# vl4e3.net
KiCad netlist of a schematic drawn in EAGLE
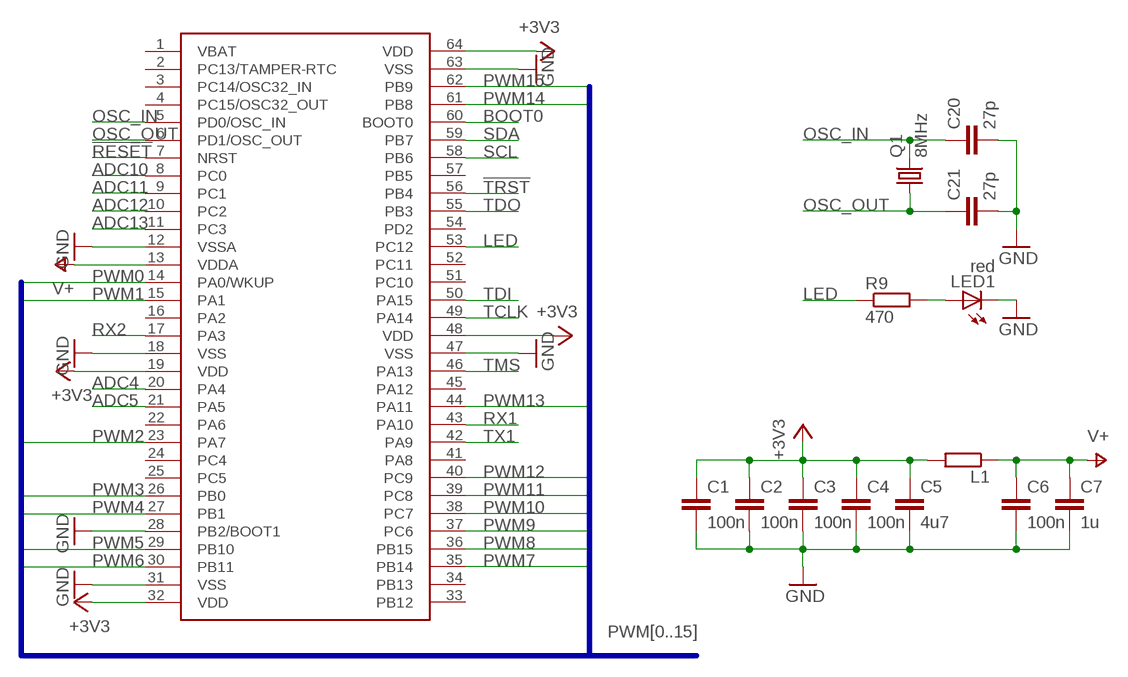
[diagram p0: schematic, sheet 1]
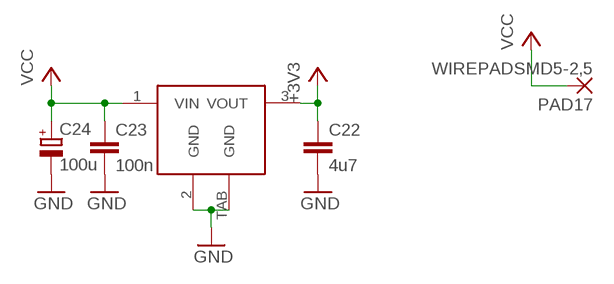
[diagram p1: schematic, sheet 2]
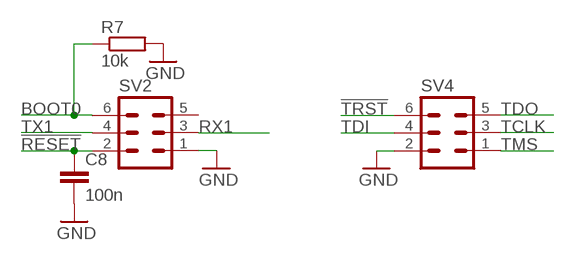
[diagram p2: schematic, sheet 3]
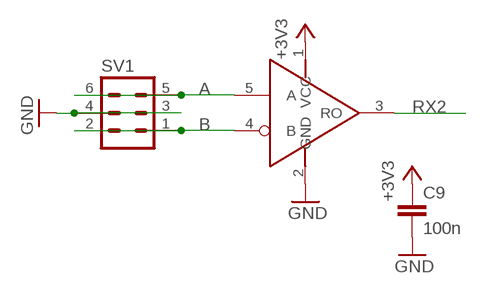
[diagram p3: schematic, sheet 4]
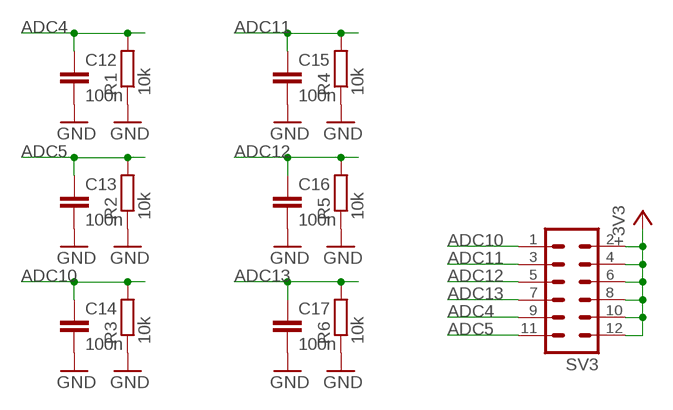
[diagram p4: schematic, sheet 5]
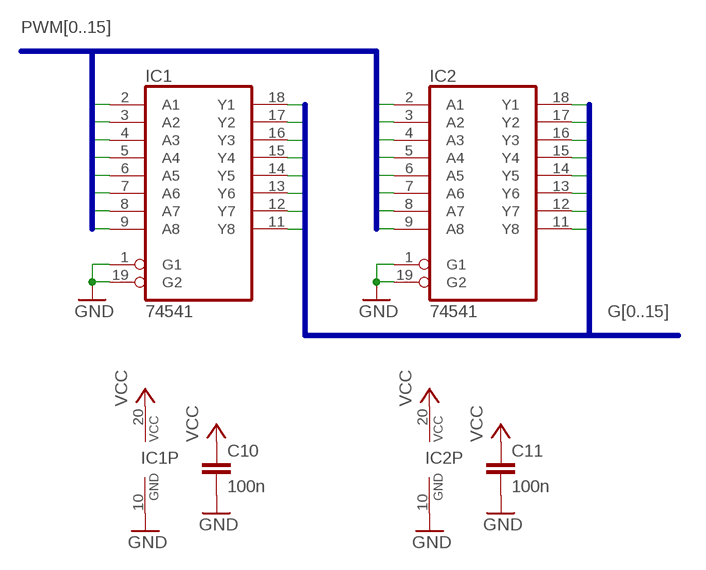
[diagram p5: schematic, sheet 6]
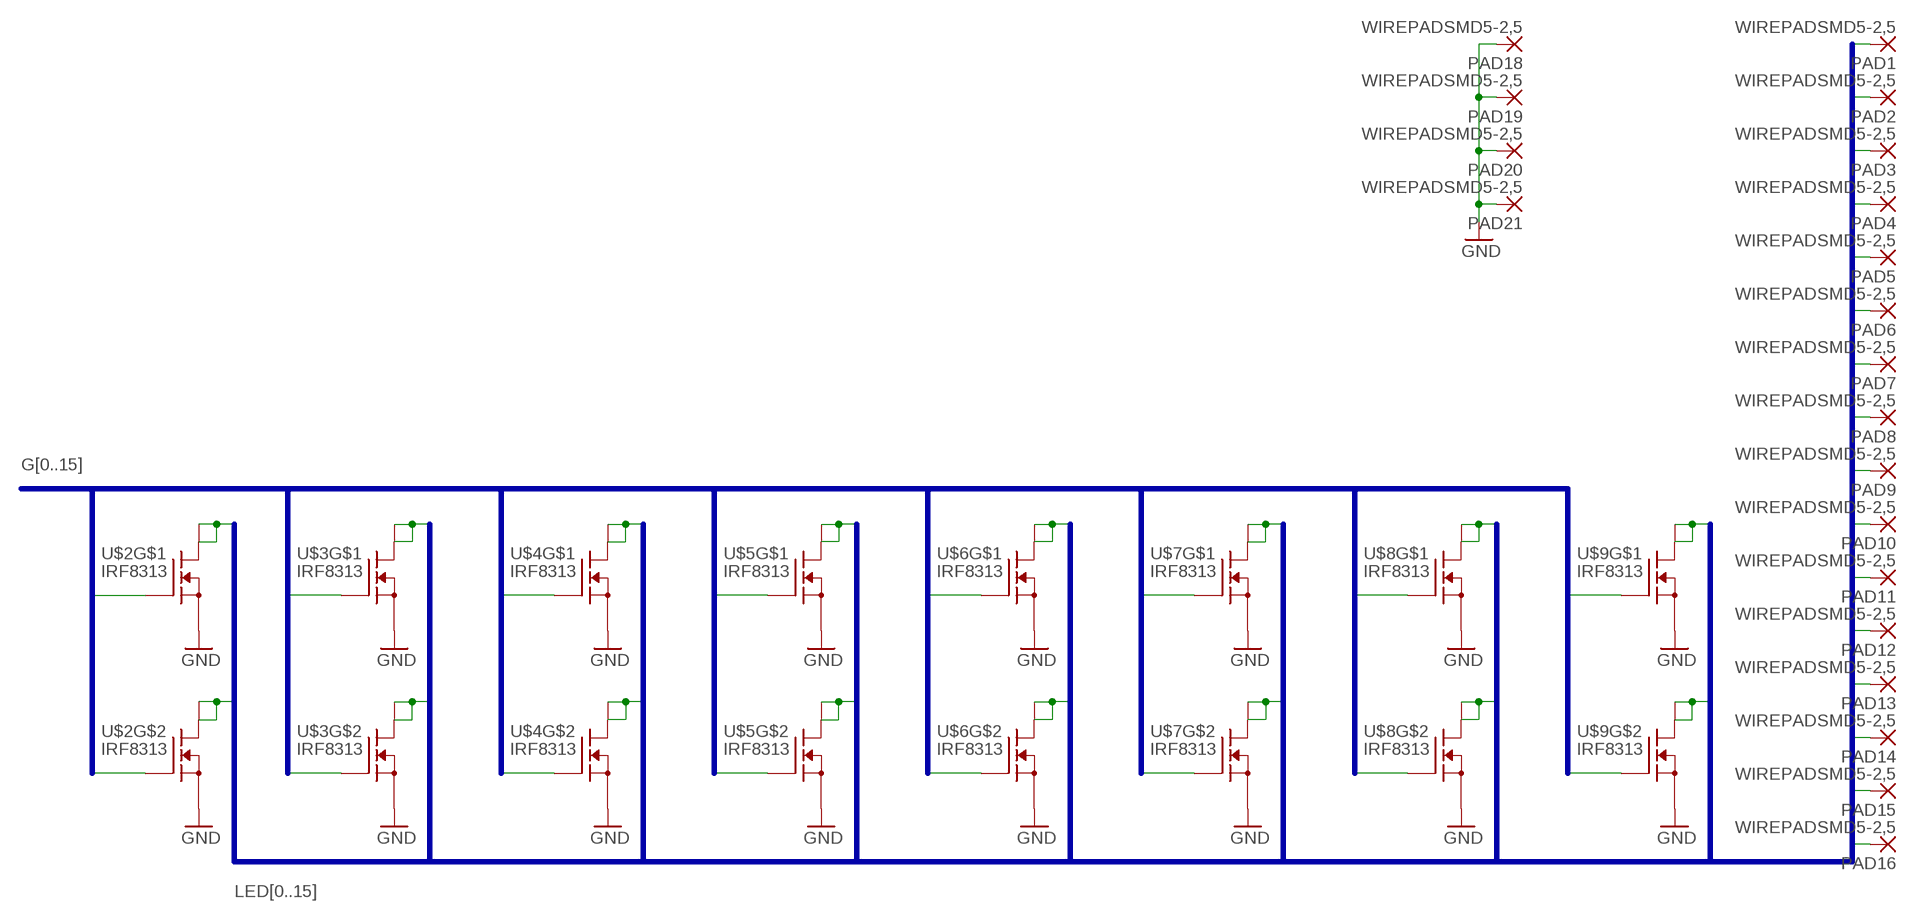
[diagram p6: schematic, sheet 7]

(export (version "E")
  (design (tool "Eeschema 10.0.6"))
  (components
    (comp (ref "C9")
      (value "100n")
      (footprint "eagle-import:C0603")
      (libsource (lib "eagle-import") (part "C-EUC0603"))
    )
    (comp (ref "SV1")
      (value "MA03-2")
      (footprint "eagle-import:MA03-2")
      (libsource (lib "eagle-import") (part "MA03-2"))
    )
    (comp (ref "U$13")
      (value "ISL3280E")
      (footprint "eagle-import:SOT23-5L")
      (libsource (lib "eagle-import") (part "ISL3280E"))
    )
    (comp (ref "C8")
      (value "100n")
      (footprint "eagle-import:C0603")
      (libsource (lib "eagle-import") (part "C-EUC0603"))
    )
    (comp (ref "R7")
      (value "10k")
      (footprint "eagle-import:R0603")
      (libsource (lib "eagle-import") (part "R-EU_R0603"))
    )
    (comp (ref "SV2")
      (value "MA03-2")
      (footprint "eagle-import:MA03-2")
      (libsource (lib "eagle-import") (part "MA03-2"))
    )
    (comp (ref "SV4")
      (value "MA03-2")
      (footprint "eagle-import:MA03-2")
      (libsource (lib "eagle-import") (part "MA03-2"))
    )
    (comp (ref "C10")
      (value "100n")
      (footprint "eagle-import:C0603")
      (libsource (lib "eagle-import") (part "C-EUC0603"))
    )
    (comp (ref "C11")
      (value "100n")
      (footprint "eagle-import:C0603")
      (libsource (lib "eagle-import") (part "C-EUC0603"))
    )
    (comp (ref "IC1")
      (value "74541")
      (footprint "eagle-import:TSSOP20")
      (libsource (lib "eagle-import") (part "74541"))
    )
    (comp (ref "IC2")
      (value "74541")
      (footprint "eagle-import:TSSOP20")
      (libsource (lib "eagle-import") (part "74541"))
    )
    (comp (ref "C1")
      (value "100n")
      (footprint "eagle-import:C0603")
      (libsource (lib "eagle-import") (part "C-EUC0603"))
    )
    (comp (ref "C2")
      (value "100n")
      (footprint "eagle-import:C0603")
      (libsource (lib "eagle-import") (part "C-EUC0603"))
    )
    (comp (ref "C3")
      (value "100n")
      (footprint "eagle-import:C0603")
      (libsource (lib "eagle-import") (part "C-EUC0603"))
    )
    (comp (ref "C4")
      (value "100n")
      (footprint "eagle-import:C0603")
      (libsource (lib "eagle-import") (part "C-EUC0603"))
    )
    (comp (ref "C5")
      (value "4u7")
      (footprint "eagle-import:C0805")
      (libsource (lib "eagle-import") (part "C-EUC0805"))
    )
    (comp (ref "C6")
      (value "100n")
      (footprint "eagle-import:C0603")
      (libsource (lib "eagle-import") (part "C-EUC0603"))
    )
    (comp (ref "C7")
      (value "1u")
      (footprint "eagle-import:C0805")
      (libsource (lib "eagle-import") (part "C-EUC0805"))
    )
    (comp (ref "C20")
      (value "27p")
      (footprint "eagle-import:C0603")
      (libsource (lib "eagle-import") (part "C-EUC0603"))
    )
    (comp (ref "C21")
      (value "27p")
      (footprint "eagle-import:C0603")
      (libsource (lib "eagle-import") (part "C-EUC0603"))
    )
    (comp (ref "L1")
      (value "R-EU_R0805")
      (footprint "eagle-import:R0805")
      (libsource (lib "eagle-import") (part "R-EU_R0805"))
    )
    (comp (ref "LED1")
      (value "red")
      (footprint "eagle-import:CHIPLED_0805")
      (libsource (lib "eagle-import") (part "LEDCHIPLED_0805"))
    )
    (comp (ref "Q1")
      (value "8MHz")
      (footprint "eagle-import:HC49_S")
      (libsource (lib "eagle-import") (part "CRYSTALHC49S"))
    )
    (comp (ref "R9")
      (value "470")
      (footprint "eagle-import:R0805")
      (libsource (lib "eagle-import") (part "R-EU_R0805"))
    )
    (comp (ref "U$1")
      (value "STM32F100R")
      (footprint "eagle-import:TQFP64-10X10")
      (libsource (lib "eagle-import") (part "STM32F100R"))
    )
    (comp (ref "PAD1")
      (value "WIREPADSMD5-2,5")
      (footprint "eagle-import:5-2,5")
      (libsource (lib "eagle-import") (part "WIREPADSMD5-2,5"))
    )
    (comp (ref "PAD2")
      (value "WIREPADSMD5-2,5")
      (footprint "eagle-import:5-2,5")
      (libsource (lib "eagle-import") (part "WIREPADSMD5-2,5"))
    )
    (comp (ref "PAD3")
      (value "WIREPADSMD5-2,5")
      (footprint "eagle-import:5-2,5")
      (libsource (lib "eagle-import") (part "WIREPADSMD5-2,5"))
    )
    (comp (ref "PAD4")
      (value "WIREPADSMD5-2,5")
      (footprint "eagle-import:5-2,5")
      (libsource (lib "eagle-import") (part "WIREPADSMD5-2,5"))
    )
    (comp (ref "PAD5")
      (value "WIREPADSMD5-2,5")
      (footprint "eagle-import:5-2,5")
      (libsource (lib "eagle-import") (part "WIREPADSMD5-2,5"))
    )
    (comp (ref "PAD6")
      (value "WIREPADSMD5-2,5")
      (footprint "eagle-import:5-2,5")
      (libsource (lib "eagle-import") (part "WIREPADSMD5-2,5"))
    )
    (comp (ref "PAD7")
      (value "WIREPADSMD5-2,5")
      (footprint "eagle-import:5-2,5")
      (libsource (lib "eagle-import") (part "WIREPADSMD5-2,5"))
    )
    (comp (ref "PAD8")
      (value "WIREPADSMD5-2,5")
      (footprint "eagle-import:5-2,5")
      (libsource (lib "eagle-import") (part "WIREPADSMD5-2,5"))
    )
    (comp (ref "PAD9")
      (value "WIREPADSMD5-2,5")
      (footprint "eagle-import:5-2,5")
      (libsource (lib "eagle-import") (part "WIREPADSMD5-2,5"))
    )
    (comp (ref "PAD10")
      (value "WIREPADSMD5-2,5")
      (footprint "eagle-import:5-2,5")
      (libsource (lib "eagle-import") (part "WIREPADSMD5-2,5"))
    )
    (comp (ref "PAD11")
      (value "WIREPADSMD5-2,5")
      (footprint "eagle-import:5-2,5")
      (libsource (lib "eagle-import") (part "WIREPADSMD5-2,5"))
    )
    (comp (ref "PAD12")
      (value "WIREPADSMD5-2,5")
      (footprint "eagle-import:5-2,5")
      (libsource (lib "eagle-import") (part "WIREPADSMD5-2,5"))
    )
    (comp (ref "PAD13")
      (value "WIREPADSMD5-2,5")
      (footprint "eagle-import:5-2,5")
      (libsource (lib "eagle-import") (part "WIREPADSMD5-2,5"))
    )
    (comp (ref "PAD14")
      (value "WIREPADSMD5-2,5")
      (footprint "eagle-import:5-2,5")
      (libsource (lib "eagle-import") (part "WIREPADSMD5-2,5"))
    )
    (comp (ref "PAD15")
      (value "WIREPADSMD5-2,5")
      (footprint "eagle-import:5-2,5")
      (libsource (lib "eagle-import") (part "WIREPADSMD5-2,5"))
    )
    (comp (ref "PAD16")
      (value "WIREPADSMD5-2,5")
      (footprint "eagle-import:5-2,5")
      (libsource (lib "eagle-import") (part "WIREPADSMD5-2,5"))
    )
    (comp (ref "PAD18")
      (value "WIREPADSMD5-2,5")
      (footprint "eagle-import:5-2,5")
      (libsource (lib "eagle-import") (part "WIREPADSMD5-2,5"))
    )
    (comp (ref "PAD19")
      (value "WIREPADSMD5-2,5")
      (footprint "eagle-import:5-2,5")
      (libsource (lib "eagle-import") (part "WIREPADSMD5-2,5"))
    )
    (comp (ref "PAD20")
      (value "WIREPADSMD5-2,5")
      (footprint "eagle-import:5-2,5")
      (libsource (lib "eagle-import") (part "WIREPADSMD5-2,5"))
    )
    (comp (ref "PAD21")
      (value "WIREPADSMD5-2,5")
      (footprint "eagle-import:5-2,5")
      (libsource (lib "eagle-import") (part "WIREPADSMD5-2,5"))
    )
    (comp (ref "U$2")
      (value "IRF8313")
      (footprint "eagle-import:SO-08")
      (libsource (lib "eagle-import") (part "IRF8313"))
    )
    (comp (ref "U$3")
      (value "IRF8313")
      (footprint "eagle-import:SO-08")
      (libsource (lib "eagle-import") (part "IRF8313"))
    )
    (comp (ref "U$4")
      (value "IRF8313")
      (footprint "eagle-import:SO-08")
      (libsource (lib "eagle-import") (part "IRF8313"))
    )
    (comp (ref "U$5")
      (value "IRF8313")
      (footprint "eagle-import:SO-08")
      (libsource (lib "eagle-import") (part "IRF8313"))
    )
    (comp (ref "U$6")
      (value "IRF8313")
      (footprint "eagle-import:SO-08")
      (libsource (lib "eagle-import") (part "IRF8313"))
    )
    (comp (ref "U$7")
      (value "IRF8313")
      (footprint "eagle-import:SO-08")
      (libsource (lib "eagle-import") (part "IRF8313"))
    )
    (comp (ref "U$8")
      (value "IRF8313")
      (footprint "eagle-import:SO-08")
      (libsource (lib "eagle-import") (part "IRF8313"))
    )
    (comp (ref "U$9")
      (value "IRF8313")
      (footprint "eagle-import:SO-08")
      (libsource (lib "eagle-import") (part "IRF8313"))
    )
    (comp (ref "C22")
      (value "4u7")
      (footprint "eagle-import:C0805")
      (libsource (lib "eagle-import") (part "C-EUC0805"))
    )
    (comp (ref "C23")
      (value "100n")
      (footprint "eagle-import:C0603")
      (libsource (lib "eagle-import") (part "C-EUC0603"))
    )
    (comp (ref "C24")
      (value "100u")
      (footprint "eagle-import:E2,5-6")
      (libsource (lib "eagle-import") (part "CPOL-EUE2.5-6"))
    )
    (comp (ref "PAD17")
      (value "WIREPADSMD5-2,5")
      (footprint "eagle-import:5-2,5")
      (libsource (lib "eagle-import") (part "WIREPADSMD5-2,5"))
    )
    (comp (ref "U$10")
      (value "MIC5209")
      (footprint "eagle-import:SOT223")
      (libsource (lib "eagle-import") (part "MIC5209"))
    )
    (comp (ref "C12")
      (value "100n")
      (footprint "eagle-import:C0603")
      (libsource (lib "eagle-import") (part "C-EUC0603"))
    )
    (comp (ref "C13")
      (value "100n")
      (footprint "eagle-import:C0603")
      (libsource (lib "eagle-import") (part "C-EUC0603"))
    )
    (comp (ref "C14")
      (value "100n")
      (footprint "eagle-import:C0603")
      (libsource (lib "eagle-import") (part "C-EUC0603"))
    )
    (comp (ref "C15")
      (value "100n")
      (footprint "eagle-import:C0603")
      (libsource (lib "eagle-import") (part "C-EUC0603"))
    )
    (comp (ref "C16")
      (value "100n")
      (footprint "eagle-import:C0603")
      (libsource (lib "eagle-import") (part "C-EUC0603"))
    )
    (comp (ref "C17")
      (value "100n")
      (footprint "eagle-import:C0603")
      (libsource (lib "eagle-import") (part "C-EUC0603"))
    )
    (comp (ref "R1")
      (value "10k")
      (footprint "eagle-import:R0603")
      (libsource (lib "eagle-import") (part "R-EU_R0603"))
    )
    (comp (ref "R2")
      (value "10k")
      (footprint "eagle-import:R0603")
      (libsource (lib "eagle-import") (part "R-EU_R0603"))
    )
    (comp (ref "R3")
      (value "10k")
      (footprint "eagle-import:R0603")
      (libsource (lib "eagle-import") (part "R-EU_R0603"))
    )
    (comp (ref "R4")
      (value "10k")
      (footprint "eagle-import:R0603")
      (libsource (lib "eagle-import") (part "R-EU_R0603"))
    )
    (comp (ref "R5")
      (value "10k")
      (footprint "eagle-import:R0603")
      (libsource (lib "eagle-import") (part "R-EU_R0603"))
    )
    (comp (ref "R6")
      (value "10k")
      (footprint "eagle-import:R0603")
      (libsource (lib "eagle-import") (part "R-EU_R0603"))
    )
    (comp (ref "SV3")
      (value "MA06-2")
      (footprint "eagle-import:MA06-2")
      (libsource (lib "eagle-import") (part "MA06-2"))
    )
  )
  (nets
    (net (code "1") (name "+3V3") (class "Default")
      (node (ref "C1") (pin "1") (pinfunction "1_1") (pintype "passive"))
      (node (ref "C2") (pin "1") (pinfunction "1_1") (pintype "passive"))
      (node (ref "C22") (pin "1") (pinfunction "1_1") (pintype "passive"))
      (node (ref "C3") (pin "1") (pinfunction "1_1") (pintype "passive"))
      (node (ref "C4") (pin "1") (pinfunction "1_1") (pintype "passive"))
      (node (ref "C5") (pin "1") (pinfunction "1_1") (pintype "passive"))
      (node (ref "C9") (pin "1") (pinfunction "1_1") (pintype "passive"))
      (node (ref "L1") (pin "2") (pinfunction "2_2") (pintype "passive"))
      (node (ref "SV3") (pin "10") (pinfunction "10_10") (pintype "passive"))
      (node (ref "SV3") (pin "12") (pinfunction "12_12") (pintype "passive"))
      (node (ref "SV3") (pin "2") (pinfunction "2_2") (pintype "passive"))
      (node (ref "SV3") (pin "4") (pinfunction "4_4") (pintype "passive"))
      (node (ref "SV3") (pin "6") (pinfunction "6_6") (pintype "passive"))
      (node (ref "SV3") (pin "8") (pinfunction "8_8") (pintype "passive"))
      (node (ref "U$1") (pin "19") (pinfunction "VDD_19") (pintype "bidirectional"))
      (node (ref "U$1") (pin "32") (pinfunction "VDD_32") (pintype "bidirectional"))
      (node (ref "U$1") (pin "48") (pinfunction "VDD_48") (pintype "bidirectional"))
      (node (ref "U$1") (pin "64") (pinfunction "VDD_64") (pintype "bidirectional"))
      (node (ref "U$10") (pin "3") (pinfunction "VOUT_3") (pintype "bidirectional"))
      (node (ref "U$13") (pin "1") (pinfunction "VCC_1") (pintype "power_in"))
    )
    (net (code "7") (name "A") (class "Default")
      (node (ref "SV1") (pin "5") (pinfunction "5_5") (pintype "passive"))
      (node (ref "SV1") (pin "6") (pinfunction "6_6") (pintype "passive"))
      (node (ref "U$13") (pin "5") (pinfunction "A_5") (pintype "bidirectional"))
    )
    (net (code "8") (name "ADC4") (class "Default")
      (node (ref "C12") (pin "1") (pinfunction "1_1") (pintype "passive"))
      (node (ref "R1") (pin "2") (pinfunction "2_2") (pintype "passive"))
      (node (ref "SV3") (pin "9") (pinfunction "9_9") (pintype "passive"))
      (node (ref "U$1") (pin "20") (pinfunction "PA4_20") (pintype "bidirectional"))
    )
    (net (code "9") (name "ADC5") (class "Default")
      (node (ref "C13") (pin "1") (pinfunction "1_1") (pintype "passive"))
      (node (ref "R2") (pin "2") (pinfunction "2_2") (pintype "passive"))
      (node (ref "SV3") (pin "11") (pinfunction "11_11") (pintype "passive"))
      (node (ref "U$1") (pin "21") (pinfunction "PA5_21") (pintype "bidirectional"))
    )
    (net (code "10") (name "ADC10") (class "Default")
      (node (ref "C14") (pin "1") (pinfunction "1_1") (pintype "passive"))
      (node (ref "R3") (pin "2") (pinfunction "2_2") (pintype "passive"))
      (node (ref "SV3") (pin "1") (pinfunction "1_1") (pintype "passive"))
      (node (ref "U$1") (pin "8") (pinfunction "PC0_8") (pintype "bidirectional"))
    )
    (net (code "11") (name "ADC11") (class "Default")
      (node (ref "C15") (pin "1") (pinfunction "1_1") (pintype "passive"))
      (node (ref "R4") (pin "2") (pinfunction "2_2") (pintype "passive"))
      (node (ref "SV3") (pin "3") (pinfunction "3_3") (pintype "passive"))
      (node (ref "U$1") (pin "9") (pinfunction "PC1_9") (pintype "bidirectional"))
    )
    (net (code "12") (name "ADC12") (class "Default")
      (node (ref "C16") (pin "1") (pinfunction "1_1") (pintype "passive"))
      (node (ref "R5") (pin "2") (pinfunction "2_2") (pintype "passive"))
      (node (ref "SV3") (pin "5") (pinfunction "5_5") (pintype "passive"))
      (node (ref "U$1") (pin "10") (pinfunction "PC2_10") (pintype "bidirectional"))
    )
    (net (code "13") (name "ADC13") (class "Default")
      (node (ref "C17") (pin "1") (pinfunction "1_1") (pintype "passive"))
      (node (ref "R6") (pin "2") (pinfunction "2_2") (pintype "passive"))
      (node (ref "SV3") (pin "7") (pinfunction "7_7") (pintype "passive"))
      (node (ref "U$1") (pin "11") (pinfunction "PC3_11") (pintype "bidirectional"))
    )
    (net (code "14") (name "B") (class "Default")
      (node (ref "SV1") (pin "1") (pinfunction "1_1") (pintype "passive"))
      (node (ref "SV1") (pin "2") (pinfunction "2_2") (pintype "passive"))
      (node (ref "U$13") (pin "4") (pinfunction "B_4") (pintype "bidirectional"))
    )
    (net (code "15") (name "BOOT0") (class "Default")
      (node (ref "R7") (pin "1") (pinfunction "1_1") (pintype "passive"))
      (node (ref "SV2") (pin "6") (pinfunction "6_6") (pintype "passive"))
      (node (ref "U$1") (pin "60") (pinfunction "BOOT0_60") (pintype "bidirectional"))
    )
    (net (code "16") (name "G0") (class "Default")
      (node (ref "IC1") (pin "18") (pinfunction "Y1_18") (pintype "tri_state"))
      (node (ref "U$2") (pin "2") (pinfunction "G_2") (pintype "passive"))
    )
    (net (code "17") (name "G1") (class "Default")
      (node (ref "IC1") (pin "17") (pinfunction "Y2_17") (pintype "tri_state"))
      (node (ref "U$2") (pin "4") (pinfunction "G_4") (pintype "passive"))
    )
    (net (code "18") (name "G2") (class "Default")
      (node (ref "IC1") (pin "16") (pinfunction "Y3_16") (pintype "tri_state"))
      (node (ref "U$3") (pin "2") (pinfunction "G_2") (pintype "passive"))
    )
    (net (code "19") (name "G3") (class "Default")
      (node (ref "IC1") (pin "15") (pinfunction "Y4_15") (pintype "tri_state"))
      (node (ref "U$3") (pin "4") (pinfunction "G_4") (pintype "passive"))
    )
    (net (code "20") (name "G4") (class "Default")
      (node (ref "IC1") (pin "14") (pinfunction "Y5_14") (pintype "tri_state"))
      (node (ref "U$4") (pin "2") (pinfunction "G_2") (pintype "passive"))
    )
    (net (code "21") (name "G5") (class "Default")
      (node (ref "IC1") (pin "13") (pinfunction "Y6_13") (pintype "tri_state"))
      (node (ref "U$4") (pin "4") (pinfunction "G_4") (pintype "passive"))
    )
    (net (code "22") (name "G6") (class "Default")
      (node (ref "IC1") (pin "12") (pinfunction "Y7_12") (pintype "tri_state"))
      (node (ref "U$5") (pin "2") (pinfunction "G_2") (pintype "passive"))
    )
    (net (code "23") (name "G7") (class "Default")
      (node (ref "IC1") (pin "11") (pinfunction "Y8_11") (pintype "tri_state"))
      (node (ref "U$5") (pin "4") (pinfunction "G_4") (pintype "passive"))
    )
    (net (code "24") (name "G8") (class "Default")
      (node (ref "IC2") (pin "18") (pinfunction "Y1_18") (pintype "tri_state"))
      (node (ref "U$6") (pin "2") (pinfunction "G_2") (pintype "passive"))
    )
    (net (code "25") (name "G9") (class "Default")
      (node (ref "IC2") (pin "17") (pinfunction "Y2_17") (pintype "tri_state"))
      (node (ref "U$6") (pin "4") (pinfunction "G_4") (pintype "passive"))
    )
    (net (code "26") (name "G10") (class "Default")
      (node (ref "IC2") (pin "16") (pinfunction "Y3_16") (pintype "tri_state"))
      (node (ref "U$7") (pin "2") (pinfunction "G_2") (pintype "passive"))
    )
    (net (code "27") (name "G11") (class "Default")
      (node (ref "IC2") (pin "15") (pinfunction "Y4_15") (pintype "tri_state"))
      (node (ref "U$7") (pin "4") (pinfunction "G_4") (pintype "passive"))
    )
    (net (code "28") (name "G12") (class "Default")
      (node (ref "IC2") (pin "14") (pinfunction "Y5_14") (pintype "tri_state"))
      (node (ref "U$8") (pin "2") (pinfunction "G_2") (pintype "passive"))
    )
    (net (code "29") (name "G13") (class "Default")
      (node (ref "IC2") (pin "13") (pinfunction "Y6_13") (pintype "tri_state"))
      (node (ref "U$8") (pin "4") (pinfunction "G_4") (pintype "passive"))
    )
    (net (code "30") (name "G14") (class "Default")
      (node (ref "IC2") (pin "12") (pinfunction "Y7_12") (pintype "tri_state"))
      (node (ref "U$9") (pin "2") (pinfunction "G_2") (pintype "passive"))
    )
    (net (code "31") (name "G15") (class "Default")
      (node (ref "IC2") (pin "11") (pinfunction "Y8_11") (pintype "tri_state"))
      (node (ref "U$9") (pin "4") (pinfunction "G_4") (pintype "passive"))
    )
    (net (code "32") (name "GND") (class "Default")
      (node (ref "C1") (pin "2") (pinfunction "2_2") (pintype "passive"))
      (node (ref "C10") (pin "2") (pinfunction "2_2") (pintype "passive"))
      (node (ref "C11") (pin "2") (pinfunction "2_2") (pintype "passive"))
      (node (ref "C12") (pin "2") (pinfunction "2_2") (pintype "passive"))
      (node (ref "C13") (pin "2") (pinfunction "2_2") (pintype "passive"))
      (node (ref "C14") (pin "2") (pinfunction "2_2") (pintype "passive"))
      (node (ref "C15") (pin "2") (pinfunction "2_2") (pintype "passive"))
      (node (ref "C16") (pin "2") (pinfunction "2_2") (pintype "passive"))
      (node (ref "C17") (pin "2") (pinfunction "2_2") (pintype "passive"))
      (node (ref "C2") (pin "2") (pinfunction "2_2") (pintype "passive"))
      (node (ref "C20") (pin "2") (pinfunction "2_2") (pintype "passive"))
      (node (ref "C21") (pin "2") (pinfunction "2_2") (pintype "passive"))
      (node (ref "C22") (pin "2") (pinfunction "2_2") (pintype "passive"))
      (node (ref "C23") (pin "2") (pinfunction "2_2") (pintype "passive"))
      (node (ref "C24") (pin "-") (pinfunction "-_-") (pintype "passive"))
      (node (ref "C3") (pin "2") (pinfunction "2_2") (pintype "passive"))
      (node (ref "C4") (pin "2") (pinfunction "2_2") (pintype "passive"))
      (node (ref "C5") (pin "2") (pinfunction "2_2") (pintype "passive"))
      (node (ref "C6") (pin "2") (pinfunction "2_2") (pintype "passive"))
      (node (ref "C7") (pin "2") (pinfunction "2_2") (pintype "passive"))
      (node (ref "C8") (pin "2") (pinfunction "2_2") (pintype "passive"))
      (node (ref "C9") (pin "2") (pinfunction "2_2") (pintype "passive"))
      (node (ref "IC1") (pin "1") (pinfunction "G1_1") (pintype "input"))
      (node (ref "IC1") (pin "10") (pinfunction "GND_10") (pintype "power_in"))
      (node (ref "IC1") (pin "19") (pinfunction "G2_19") (pintype "input"))
      (node (ref "IC2") (pin "1") (pinfunction "G1_1") (pintype "input"))
      (node (ref "IC2") (pin "10") (pinfunction "GND_10") (pintype "power_in"))
      (node (ref "IC2") (pin "19") (pinfunction "G2_19") (pintype "input"))
      (node (ref "LED1") (pin "C") (pinfunction "C_C") (pintype "passive"))
      (node (ref "PAD18") (pin "1") (pinfunction "P_1") (pintype "passive"))
      (node (ref "PAD19") (pin "1") (pinfunction "P_1") (pintype "passive"))
      (node (ref "PAD20") (pin "1") (pinfunction "P_1") (pintype "passive"))
      (node (ref "PAD21") (pin "1") (pinfunction "P_1") (pintype "passive"))
      (node (ref "R1") (pin "1") (pinfunction "1_1") (pintype "passive"))
      (node (ref "R2") (pin "1") (pinfunction "1_1") (pintype "passive"))
      (node (ref "R3") (pin "1") (pinfunction "1_1") (pintype "passive"))
      (node (ref "R4") (pin "1") (pinfunction "1_1") (pintype "passive"))
      (node (ref "R5") (pin "1") (pinfunction "1_1") (pintype "passive"))
      (node (ref "R6") (pin "1") (pinfunction "1_1") (pintype "passive"))
      (node (ref "R7") (pin "2") (pinfunction "2_2") (pintype "passive"))
      (node (ref "SV1") (pin "3") (pinfunction "3_3") (pintype "passive"))
      (node (ref "SV1") (pin "4") (pinfunction "4_4") (pintype "passive"))
      (node (ref "SV2") (pin "1") (pinfunction "1_1") (pintype "passive"))
      (node (ref "SV4") (pin "2") (pinfunction "2_2") (pintype "passive"))
      (node (ref "U$1") (pin "12") (pinfunction "VSSA_12") (pintype "bidirectional"))
      (node (ref "U$1") (pin "18") (pinfunction "VSS_18") (pintype "bidirectional"))
      (node (ref "U$1") (pin "28") (pinfunction "PB2/BOOT1_28") (pintype "bidirectional"))
      (node (ref "U$1") (pin "31") (pinfunction "VSS_31") (pintype "bidirectional"))
      (node (ref "U$1") (pin "47") (pinfunction "VSS_47") (pintype "bidirectional"))
      (node (ref "U$1") (pin "63") (pinfunction "VSS_63") (pintype "bidirectional"))
      (node (ref "U$10") (pin "2") (pinfunction "GND_2") (pintype "bidirectional"))
      (node (ref "U$10") (pin "TAB") (pinfunction "GND_TAB") (pintype "bidirectional"))
      (node (ref "U$13") (pin "2") (pinfunction "GND_2") (pintype "power_in"))
      (node (ref "U$2") (pin "1") (pinfunction "S_1") (pintype "passive"))
      (node (ref "U$2") (pin "3") (pinfunction "S_3") (pintype "passive"))
      (node (ref "U$3") (pin "1") (pinfunction "S_1") (pintype "passive"))
      (node (ref "U$3") (pin "3") (pinfunction "S_3") (pintype "passive"))
      (node (ref "U$4") (pin "1") (pinfunction "S_1") (pintype "passive"))
      (node (ref "U$4") (pin "3") (pinfunction "S_3") (pintype "passive"))
      (node (ref "U$5") (pin "1") (pinfunction "S_1") (pintype "passive"))
      (node (ref "U$5") (pin "3") (pinfunction "S_3") (pintype "passive"))
      (node (ref "U$6") (pin "1") (pinfunction "S_1") (pintype "passive"))
      (node (ref "U$6") (pin "3") (pinfunction "S_3") (pintype "passive"))
      (node (ref "U$7") (pin "1") (pinfunction "S_1") (pintype "passive"))
      (node (ref "U$7") (pin "3") (pinfunction "S_3") (pintype "passive"))
      (node (ref "U$8") (pin "1") (pinfunction "S_1") (pintype "passive"))
      (node (ref "U$8") (pin "3") (pinfunction "S_3") (pintype "passive"))
      (node (ref "U$9") (pin "1") (pinfunction "S_1") (pintype "passive"))
      (node (ref "U$9") (pin "3") (pinfunction "S_3") (pintype "passive"))
    )
    (net (code "33") (name "LED") (class "Default")
      (node (ref "R9") (pin "1") (pinfunction "1_1") (pintype "passive"))
      (node (ref "U$1") (pin "53") (pinfunction "PC12_53") (pintype "bidirectional"))
    )
    (net (code "34") (name "LED0") (class "Default")
      (node (ref "PAD1") (pin "1") (pinfunction "P_1") (pintype "passive"))
      (node (ref "U$2") (pin "7") (pinfunction "D_7") (pintype "passive"))
      (node (ref "U$2") (pin "8") (pinfunction "D_8") (pintype "passive"))
    )
    (net (code "35") (name "LED1") (class "Default")
      (node (ref "PAD2") (pin "1") (pinfunction "P_1") (pintype "passive"))
      (node (ref "U$2") (pin "5") (pinfunction "D_5") (pintype "passive"))
      (node (ref "U$2") (pin "6") (pinfunction "D_6") (pintype "passive"))
    )
    (net (code "36") (name "LED2") (class "Default")
      (node (ref "PAD3") (pin "1") (pinfunction "P_1") (pintype "passive"))
      (node (ref "U$3") (pin "7") (pinfunction "D_7") (pintype "passive"))
      (node (ref "U$3") (pin "8") (pinfunction "D_8") (pintype "passive"))
    )
    (net (code "37") (name "LED3") (class "Default")
      (node (ref "PAD4") (pin "1") (pinfunction "P_1") (pintype "passive"))
      (node (ref "U$3") (pin "5") (pinfunction "D_5") (pintype "passive"))
      (node (ref "U$3") (pin "6") (pinfunction "D_6") (pintype "passive"))
    )
    (net (code "38") (name "LED4") (class "Default")
      (node (ref "PAD5") (pin "1") (pinfunction "P_1") (pintype "passive"))
      (node (ref "U$4") (pin "7") (pinfunction "D_7") (pintype "passive"))
      (node (ref "U$4") (pin "8") (pinfunction "D_8") (pintype "passive"))
    )
    (net (code "39") (name "LED5") (class "Default")
      (node (ref "PAD6") (pin "1") (pinfunction "P_1") (pintype "passive"))
      (node (ref "U$4") (pin "5") (pinfunction "D_5") (pintype "passive"))
      (node (ref "U$4") (pin "6") (pinfunction "D_6") (pintype "passive"))
    )
    (net (code "40") (name "LED6") (class "Default")
      (node (ref "PAD7") (pin "1") (pinfunction "P_1") (pintype "passive"))
      (node (ref "U$5") (pin "7") (pinfunction "D_7") (pintype "passive"))
      (node (ref "U$5") (pin "8") (pinfunction "D_8") (pintype "passive"))
    )
    (net (code "41") (name "LED7") (class "Default")
      (node (ref "PAD8") (pin "1") (pinfunction "P_1") (pintype "passive"))
      (node (ref "U$5") (pin "5") (pinfunction "D_5") (pintype "passive"))
      (node (ref "U$5") (pin "6") (pinfunction "D_6") (pintype "passive"))
    )
    (net (code "42") (name "LED8") (class "Default")
      (node (ref "PAD9") (pin "1") (pinfunction "P_1") (pintype "passive"))
      (node (ref "U$6") (pin "7") (pinfunction "D_7") (pintype "passive"))
      (node (ref "U$6") (pin "8") (pinfunction "D_8") (pintype "passive"))
    )
    (net (code "43") (name "LED9") (class "Default")
      (node (ref "PAD10") (pin "1") (pinfunction "P_1") (pintype "passive"))
      (node (ref "U$6") (pin "5") (pinfunction "D_5") (pintype "passive"))
      (node (ref "U$6") (pin "6") (pinfunction "D_6") (pintype "passive"))
    )
    (net (code "44") (name "LED10") (class "Default")
      (node (ref "PAD11") (pin "1") (pinfunction "P_1") (pintype "passive"))
      (node (ref "U$7") (pin "7") (pinfunction "D_7") (pintype "passive"))
      (node (ref "U$7") (pin "8") (pinfunction "D_8") (pintype "passive"))
    )
    (net (code "45") (name "LED11") (class "Default")
      (node (ref "PAD12") (pin "1") (pinfunction "P_1") (pintype "passive"))
      (node (ref "U$7") (pin "5") (pinfunction "D_5") (pintype "passive"))
      (node (ref "U$7") (pin "6") (pinfunction "D_6") (pintype "passive"))
    )
    (net (code "46") (name "LED12") (class "Default")
      (node (ref "PAD13") (pin "1") (pinfunction "P_1") (pintype "passive"))
      (node (ref "U$8") (pin "7") (pinfunction "D_7") (pintype "passive"))
      (node (ref "U$8") (pin "8") (pinfunction "D_8") (pintype "passive"))
    )
    (net (code "47") (name "LED13") (class "Default")
      (node (ref "PAD14") (pin "1") (pinfunction "P_1") (pintype "passive"))
      (node (ref "U$8") (pin "5") (pinfunction "D_5") (pintype "passive"))
      (node (ref "U$8") (pin "6") (pinfunction "D_6") (pintype "passive"))
    )
    (net (code "48") (name "LED14") (class "Default")
      (node (ref "PAD15") (pin "1") (pinfunction "P_1") (pintype "passive"))
      (node (ref "U$9") (pin "7") (pinfunction "D_7") (pintype "passive"))
      (node (ref "U$9") (pin "8") (pinfunction "D_8") (pintype "passive"))
    )
    (net (code "49") (name "LED15") (class "Default")
      (node (ref "PAD16") (pin "1") (pinfunction "P_1") (pintype "passive"))
      (node (ref "U$9") (pin "5") (pinfunction "D_5") (pintype "passive"))
      (node (ref "U$9") (pin "6") (pinfunction "D_6") (pintype "passive"))
    )
    (net (code "50") (name "Net-(LED1-PadA)") (class "Default")
      (node (ref "LED1") (pin "A") (pinfunction "A_A") (pintype "passive"))
      (node (ref "R9") (pin "2") (pinfunction "2_2") (pintype "passive"))
    )
    (net (code "51") (name "OSC_IN") (class "Default")
      (node (ref "C20") (pin "1") (pinfunction "1_1") (pintype "passive"))
      (node (ref "Q1") (pin "2") (pinfunction "2_2") (pintype "passive"))
      (node (ref "U$1") (pin "5") (pinfunction "PD0/OSC_IN_5") (pintype "bidirectional"))
    )
    (net (code "52") (name "OSC_OUT") (class "Default")
      (node (ref "C21") (pin "1") (pinfunction "1_1") (pintype "passive"))
      (node (ref "Q1") (pin "1") (pinfunction "1_1") (pintype "passive"))
      (node (ref "U$1") (pin "6") (pinfunction "PD1/OSC_OUT_6") (pintype "bidirectional"))
    )
    (net (code "53") (name "PWM0") (class "Default")
      (node (ref "IC1") (pin "2") (pinfunction "A1_2") (pintype "input"))
      (node (ref "U$1") (pin "14") (pinfunction "PA0/WKUP_14") (pintype "bidirectional"))
    )
    (net (code "54") (name "PWM1") (class "Default")
      (node (ref "IC1") (pin "3") (pinfunction "A2_3") (pintype "input"))
      (node (ref "U$1") (pin "15") (pinfunction "PA1_15") (pintype "bidirectional"))
    )
    (net (code "55") (name "PWM2") (class "Default")
      (node (ref "IC1") (pin "4") (pinfunction "A3_4") (pintype "input"))
      (node (ref "U$1") (pin "23") (pinfunction "PA7_23") (pintype "bidirectional"))
    )
    (net (code "56") (name "PWM3") (class "Default")
      (node (ref "IC1") (pin "5") (pinfunction "A4_5") (pintype "input"))
      (node (ref "U$1") (pin "26") (pinfunction "PB0_26") (pintype "bidirectional"))
    )
    (net (code "57") (name "PWM4") (class "Default")
      (node (ref "IC1") (pin "6") (pinfunction "A5_6") (pintype "input"))
      (node (ref "U$1") (pin "27") (pinfunction "PB1_27") (pintype "bidirectional"))
    )
    (net (code "58") (name "PWM5") (class "Default")
      (node (ref "IC1") (pin "7") (pinfunction "A6_7") (pintype "input"))
      (node (ref "U$1") (pin "29") (pinfunction "PB10_29") (pintype "bidirectional"))
    )
    (net (code "59") (name "PWM6") (class "Default")
      (node (ref "IC1") (pin "8") (pinfunction "A7_8") (pintype "input"))
      (node (ref "U$1") (pin "30") (pinfunction "PB11_30") (pintype "bidirectional"))
    )
    (net (code "60") (name "PWM7") (class "Default")
      (node (ref "IC1") (pin "9") (pinfunction "A8_9") (pintype "input"))
      (node (ref "U$1") (pin "35") (pinfunction "PB14_35") (pintype "bidirectional"))
    )
    (net (code "61") (name "PWM8") (class "Default")
      (node (ref "IC2") (pin "2") (pinfunction "A1_2") (pintype "input"))
      (node (ref "U$1") (pin "36") (pinfunction "PB15_36") (pintype "bidirectional"))
    )
    (net (code "62") (name "PWM9") (class "Default")
      (node (ref "IC2") (pin "3") (pinfunction "A2_3") (pintype "input"))
      (node (ref "U$1") (pin "37") (pinfunction "PC6_37") (pintype "bidirectional"))
    )
    (net (code "63") (name "PWM10") (class "Default")
      (node (ref "IC2") (pin "4") (pinfunction "A3_4") (pintype "input"))
      (node (ref "U$1") (pin "38") (pinfunction "PC7_38") (pintype "bidirectional"))
    )
    (net (code "64") (name "PWM11") (class "Default")
      (node (ref "IC2") (pin "5") (pinfunction "A4_5") (pintype "input"))
      (node (ref "U$1") (pin "39") (pinfunction "PC8_39") (pintype "bidirectional"))
    )
    (net (code "65") (name "PWM12") (class "Default")
      (node (ref "IC2") (pin "6") (pinfunction "A5_6") (pintype "input"))
      (node (ref "U$1") (pin "40") (pinfunction "PC9_40") (pintype "bidirectional"))
    )
    (net (code "66") (name "PWM13") (class "Default")
      (node (ref "IC2") (pin "7") (pinfunction "A6_7") (pintype "input"))
      (node (ref "U$1") (pin "44") (pinfunction "PA11_44") (pintype "bidirectional"))
    )
    (net (code "67") (name "PWM14") (class "Default")
      (node (ref "IC2") (pin "8") (pinfunction "A7_8") (pintype "input"))
      (node (ref "U$1") (pin "61") (pinfunction "PB8_61") (pintype "bidirectional"))
    )
    (net (code "68") (name "PWM15") (class "Default")
      (node (ref "IC2") (pin "9") (pinfunction "A8_9") (pintype "input"))
      (node (ref "U$1") (pin "62") (pinfunction "PB9_62") (pintype "bidirectional"))
    )
    (net (code "69") (name "RX1") (class "Default")
      (node (ref "SV2") (pin "3") (pinfunction "3_3") (pintype "passive"))
      (node (ref "U$1") (pin "43") (pinfunction "PA10_43") (pintype "bidirectional"))
    )
    (net (code "70") (name "RX2") (class "Default")
      (node (ref "U$1") (pin "17") (pinfunction "PA3_17") (pintype "bidirectional"))
      (node (ref "U$13") (pin "3") (pinfunction "RO_3") (pintype "bidirectional"))
    )
    (net (code "71") (name "SCL") (class "Default")
      (node (ref "U$1") (pin "58") (pinfunction "PB6_58") (pintype "bidirectional"))
    )
    (net (code "72") (name "SDA") (class "Default")
      (node (ref "U$1") (pin "59") (pinfunction "PB7_59") (pintype "bidirectional"))
    )
    (net (code "73") (name "TCLK") (class "Default")
      (node (ref "SV4") (pin "3") (pinfunction "3_3") (pintype "passive"))
      (node (ref "U$1") (pin "49") (pinfunction "PA14_49") (pintype "bidirectional"))
    )
    (net (code "74") (name "TDI") (class "Default")
      (node (ref "SV4") (pin "4") (pinfunction "4_4") (pintype "passive"))
      (node (ref "U$1") (pin "50") (pinfunction "PA15_50") (pintype "bidirectional"))
    )
    (net (code "75") (name "TDO") (class "Default")
      (node (ref "SV4") (pin "5") (pinfunction "5_5") (pintype "passive"))
      (node (ref "U$1") (pin "55") (pinfunction "PB3_55") (pintype "bidirectional"))
    )
    (net (code "76") (name "TMS") (class "Default")
      (node (ref "SV4") (pin "1") (pinfunction "1_1") (pintype "passive"))
      (node (ref "U$1") (pin "46") (pinfunction "PA13_46") (pintype "bidirectional"))
    )
    (net (code "77") (name "TX1") (class "Default")
      (node (ref "SV2") (pin "4") (pinfunction "4_4") (pintype "passive"))
      (node (ref "U$1") (pin "42") (pinfunction "PA9_42") (pintype "bidirectional"))
    )
    (net (code "78") (name "V+") (class "Default")
      (node (ref "C6") (pin "1") (pinfunction "1_1") (pintype "passive"))
      (node (ref "C7") (pin "1") (pinfunction "1_1") (pintype "passive"))
      (node (ref "L1") (pin "1") (pinfunction "1_1") (pintype "passive"))
      (node (ref "U$1") (pin "13") (pinfunction "VDDA_13") (pintype "bidirectional"))
    )
    (net (code "79") (name "VCC") (class "Default")
      (node (ref "C10") (pin "1") (pinfunction "1_1") (pintype "passive"))
      (node (ref "C11") (pin "1") (pinfunction "1_1") (pintype "passive"))
      (node (ref "C23") (pin "1") (pinfunction "1_1") (pintype "passive"))
      (node (ref "C24") (pin "+") (pinfunction "+_+") (pintype "passive"))
      (node (ref "IC1") (pin "20") (pinfunction "VCC_20") (pintype "power_in"))
      (node (ref "IC2") (pin "20") (pinfunction "VCC_20") (pintype "power_in"))
      (node (ref "PAD17") (pin "1") (pinfunction "P_1") (pintype "passive"))
      (node (ref "U$10") (pin "1") (pinfunction "VIN_1") (pintype "bidirectional"))
    )
    (net (code "80") (name "unconnected-(SV2-Pad5)") (class "Default")
      (node (ref "SV2") (pin "5") (pinfunction "5_5") (pintype "passive"))
    )
    (net (code "81") (name "unconnected-(U$1-PA2-Pad16)") (class "Default")
      (node (ref "U$1") (pin "16") (pinfunction "PA2_16") (pintype "bidirectional"))
    )
    (net (code "82") (name "unconnected-(U$1-PA6-Pad22)") (class "Default")
      (node (ref "U$1") (pin "22") (pinfunction "PA6_22") (pintype "bidirectional"))
    )
    (net (code "83") (name "unconnected-(U$1-PA8-Pad41)") (class "Default")
      (node (ref "U$1") (pin "41") (pinfunction "PA8_41") (pintype "bidirectional"))
    )
    (net (code "84") (name "unconnected-(U$1-PA12-Pad45)") (class "Default")
      (node (ref "U$1") (pin "45") (pinfunction "PA12_45") (pintype "bidirectional"))
    )
    (net (code "85") (name "unconnected-(U$1-PB5-Pad57)") (class "Default")
      (node (ref "U$1") (pin "57") (pinfunction "PB5_57") (pintype "bidirectional"))
    )
    (net (code "86") (name "unconnected-(U$1-PB12-Pad33)") (class "Default")
      (node (ref "U$1") (pin "33") (pinfunction "PB12_33") (pintype "bidirectional"))
    )
    (net (code "87") (name "unconnected-(U$1-PB13-Pad34)") (class "Default")
      (node (ref "U$1") (pin "34") (pinfunction "PB13_34") (pintype "bidirectional"))
    )
    (net (code "88") (name "unconnected-(U$1-PC4-Pad24)") (class "Default")
      (node (ref "U$1") (pin "24") (pinfunction "PC4_24") (pintype "bidirectional"))
    )
    (net (code "89") (name "unconnected-(U$1-PC5-Pad25)") (class "Default")
      (node (ref "U$1") (pin "25") (pinfunction "PC5_25") (pintype "bidirectional"))
    )
    (net (code "90") (name "unconnected-(U$1-PC10-Pad51)") (class "Default")
      (node (ref "U$1") (pin "51") (pinfunction "PC10_51") (pintype "bidirectional"))
    )
    (net (code "91") (name "unconnected-(U$1-PC11-Pad52)") (class "Default")
      (node (ref "U$1") (pin "52") (pinfunction "PC11_52") (pintype "bidirectional"))
    )
    (net (code "92") (name "unconnected-(U$1-PC13{slash}TAMPER-RTC-Pad2)") (class "Default")
      (node (ref "U$1") (pin "2") (pinfunction "PC13/TAMPER-RTC_2") (pintype "bidirectional"))
    )
    (net (code "93") (name "unconnected-(U$1-PC14{slash}OSC32_IN-Pad3)") (class "Default")
      (node (ref "U$1") (pin "3") (pinfunction "PC14/OSC32_IN_3") (pintype "bidirectional"))
    )
    (net (code "94") (name "unconnected-(U$1-PC15{slash}OSC32_OUT-Pad4)") (class "Default")
      (node (ref "U$1") (pin "4") (pinfunction "PC15/OSC32_OUT_4") (pintype "bidirectional"))
    )
    (net (code "95") (name "unconnected-(U$1-PD2-Pad54)") (class "Default")
      (node (ref "U$1") (pin "54") (pinfunction "PD2_54") (pintype "bidirectional"))
    )
    (net (code "96") (name "unconnected-(U$1-VBAT-Pad1)") (class "Default")
      (node (ref "U$1") (pin "1") (pinfunction "VBAT_1") (pintype "bidirectional"))
    )
    (net (code "97") (name "~{RESET}") (class "Default")
      (node (ref "C8") (pin "1") (pinfunction "1_1") (pintype "passive"))
      (node (ref "SV2") (pin "2") (pinfunction "2_2") (pintype "passive"))
      (node (ref "U$1") (pin "7") (pinfunction "NRST_7") (pintype "bidirectional"))
    )
    (net (code "98") (name "~{TRST}") (class "Default")
      (node (ref "SV4") (pin "6") (pinfunction "6_6") (pintype "passive"))
      (node (ref "U$1") (pin "56") (pinfunction "PB4_56") (pintype "bidirectional"))
    )
  )
)
